# keypad-ECAD.net
KiCad netlist of a schematic drawn in EAGLE
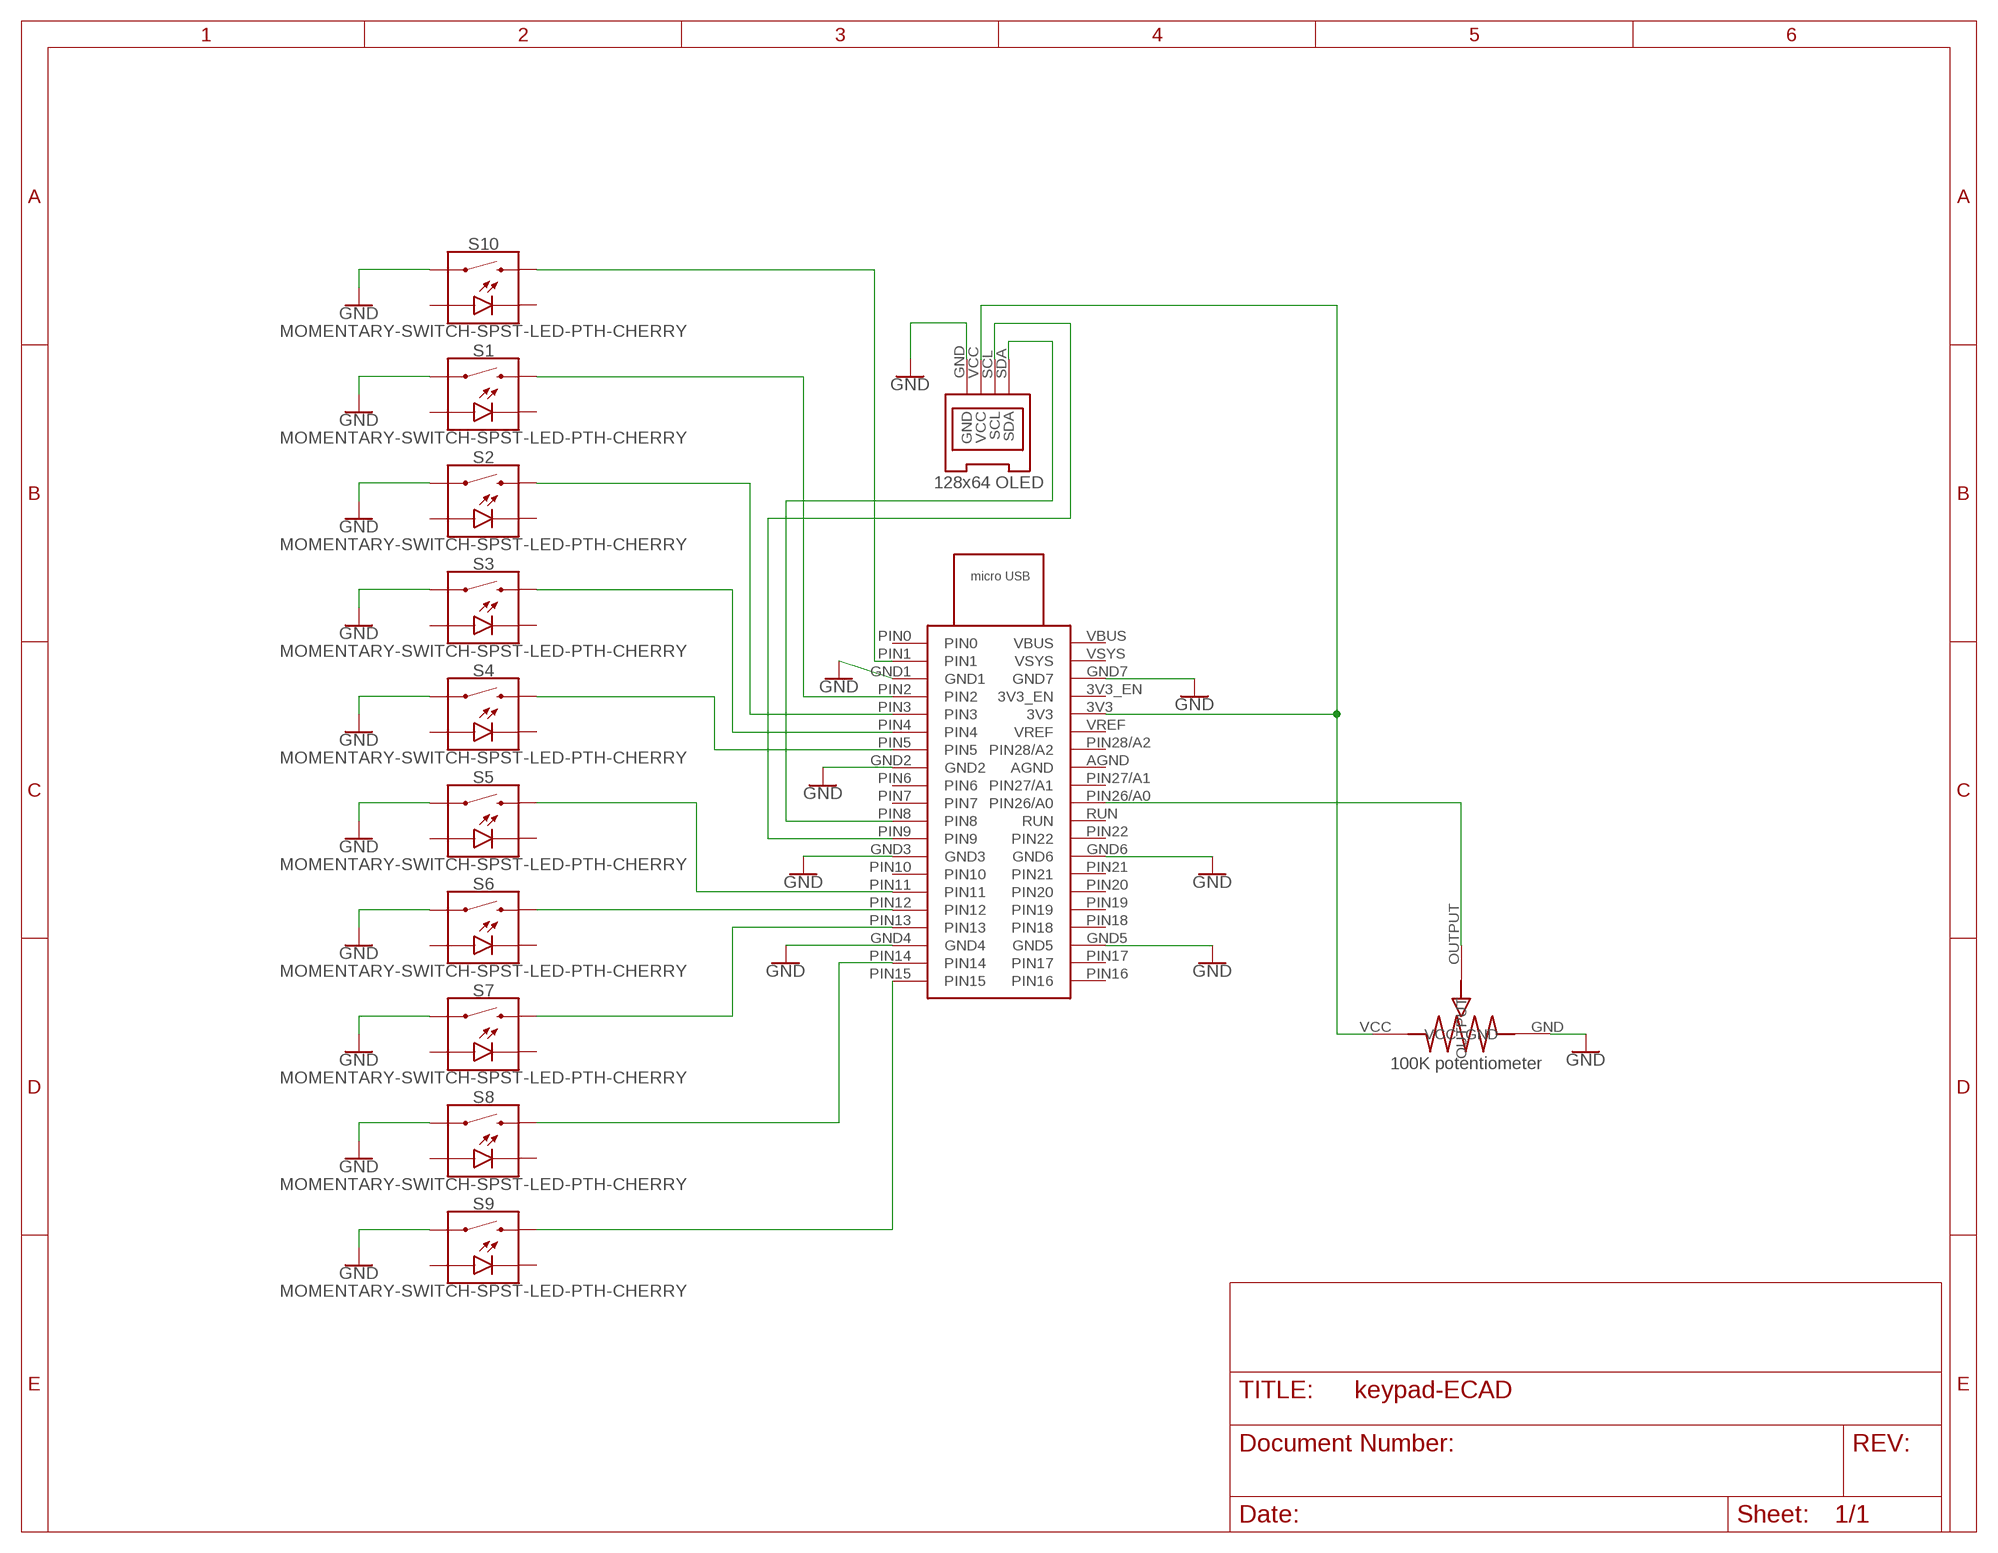
[diagram p0: schematic, sheet 1]

(export (version "E")
  (design (tool "Eeschema 10.0.6"))
  (components
    (comp (ref "S1")
      (value "MOMENTARY-SWITCH-SPST-LED-PTH-CHERRY")
      (footprint "eagle-import:CHERRY-MX-LED")
      (libsource (lib "eagle-import") (part "MOMENTARY-SWITCH-SPST-LED-PTH-CHERRY"))
    )
    (comp (ref "S2")
      (value "MOMENTARY-SWITCH-SPST-LED-PTH-CHERRY")
      (footprint "eagle-import:CHERRY-MX-LED")
      (libsource (lib "eagle-import") (part "MOMENTARY-SWITCH-SPST-LED-PTH-CHERRY"))
    )
    (comp (ref "S3")
      (value "MOMENTARY-SWITCH-SPST-LED-PTH-CHERRY")
      (footprint "eagle-import:CHERRY-MX-LED")
      (libsource (lib "eagle-import") (part "MOMENTARY-SWITCH-SPST-LED-PTH-CHERRY"))
    )
    (comp (ref "S4")
      (value "MOMENTARY-SWITCH-SPST-LED-PTH-CHERRY")
      (footprint "eagle-import:CHERRY-MX-LED")
      (libsource (lib "eagle-import") (part "MOMENTARY-SWITCH-SPST-LED-PTH-CHERRY"))
    )
    (comp (ref "S5")
      (value "MOMENTARY-SWITCH-SPST-LED-PTH-CHERRY")
      (footprint "eagle-import:CHERRY-MX-LED")
      (libsource (lib "eagle-import") (part "MOMENTARY-SWITCH-SPST-LED-PTH-CHERRY"))
    )
    (comp (ref "S6")
      (value "MOMENTARY-SWITCH-SPST-LED-PTH-CHERRY")
      (footprint "eagle-import:CHERRY-MX-LED")
      (libsource (lib "eagle-import") (part "MOMENTARY-SWITCH-SPST-LED-PTH-CHERRY"))
    )
    (comp (ref "S7")
      (value "MOMENTARY-SWITCH-SPST-LED-PTH-CHERRY")
      (footprint "eagle-import:CHERRY-MX-LED")
      (libsource (lib "eagle-import") (part "MOMENTARY-SWITCH-SPST-LED-PTH-CHERRY"))
    )
    (comp (ref "S8")
      (value "MOMENTARY-SWITCH-SPST-LED-PTH-CHERRY")
      (footprint "eagle-import:CHERRY-MX-LED")
      (libsource (lib "eagle-import") (part "MOMENTARY-SWITCH-SPST-LED-PTH-CHERRY"))
    )
    (comp (ref "S9")
      (value "MOMENTARY-SWITCH-SPST-LED-PTH-CHERRY")
      (footprint "eagle-import:CHERRY-MX-LED")
      (libsource (lib "eagle-import") (part "MOMENTARY-SWITCH-SPST-LED-PTH-CHERRY"))
    )
    (comp (ref "S10")
      (value "MOMENTARY-SWITCH-SPST-LED-PTH-CHERRY")
      (footprint "eagle-import:CHERRY-MX-LED")
      (libsource (lib "eagle-import") (part "MOMENTARY-SWITCH-SPST-LED-PTH-CHERRY"))
    )
    (comp (ref "U$1")
      (value "RP-PICO")
      (footprint "eagle-import:RP-PICO")
      (libsource (lib "eagle-import") (part "RP-PICO"))
    )
    (comp (ref "U$2")
      (value "128X64-I2C-OLED")
      (footprint "eagle-import:128X64-I2C-OLED")
      (libsource (lib "eagle-import") (part "128X64-I2C-OLED"))
    )
    (comp (ref "U$3")
      (value "KEYPAD_POT")
      (footprint "eagle-import:KEYPAD_POT")
      (libsource (lib "eagle-import") (part "KEYPAD_POT"))
    )
  )
  (nets
    (net (code "1") (name "GND") (class "Default")
      (node (ref "S1") (pin "S1") (pinfunction "1_S1") (pintype "passive"))
      (node (ref "S10") (pin "S1") (pinfunction "1_S1") (pintype "passive"))
      (node (ref "S2") (pin "S1") (pinfunction "1_S1") (pintype "passive"))
      (node (ref "S3") (pin "S1") (pinfunction "1_S1") (pintype "passive"))
      (node (ref "S4") (pin "S1") (pinfunction "1_S1") (pintype "passive"))
      (node (ref "S5") (pin "S1") (pinfunction "1_S1") (pintype "passive"))
      (node (ref "S6") (pin "S1") (pinfunction "1_S1") (pintype "passive"))
      (node (ref "S7") (pin "S1") (pinfunction "1_S1") (pintype "passive"))
      (node (ref "S8") (pin "S1") (pinfunction "1_S1") (pintype "passive"))
      (node (ref "S9") (pin "S1") (pinfunction "1_S1") (pintype "passive"))
      (node (ref "U$1") (pin "GND1") (pinfunction "GND1_GND1") (pintype "bidirectional"))
      (node (ref "U$1") (pin "GND2") (pinfunction "GND2_GND2") (pintype "bidirectional"))
      (node (ref "U$1") (pin "GND3") (pinfunction "GND3_GND3") (pintype "bidirectional"))
      (node (ref "U$1") (pin "GND4") (pinfunction "GND4_GND4") (pintype "bidirectional"))
      (node (ref "U$1") (pin "GND5") (pinfunction "GND5_GND5") (pintype "bidirectional"))
      (node (ref "U$1") (pin "GND6") (pinfunction "GND6_GND6") (pintype "bidirectional"))
      (node (ref "U$1") (pin "GND7") (pinfunction "GND7_GND7") (pintype "bidirectional"))
      (node (ref "U$2") (pin "GND") (pinfunction "GND_GND") (pintype "bidirectional"))
      (node (ref "U$3") (pin "GND") (pinfunction "GND_GND") (pintype "bidirectional"))
    )
    (net (code "2") (name "Net-(S1-2)") (class "Default")
      (node (ref "S1") (pin "S2") (pinfunction "2_S2") (pintype "passive"))
      (node (ref "U$1") (pin "PIN2") (pinfunction "PIN2_PIN2") (pintype "bidirectional"))
    )
    (net (code "3") (name "Net-(S2-2)") (class "Default")
      (node (ref "S2") (pin "S2") (pinfunction "2_S2") (pintype "passive"))
      (node (ref "U$1") (pin "PIN3") (pinfunction "PIN3_PIN3") (pintype "bidirectional"))
    )
    (net (code "4") (name "Net-(S3-2)") (class "Default")
      (node (ref "S3") (pin "S2") (pinfunction "2_S2") (pintype "passive"))
      (node (ref "U$1") (pin "PIN4") (pinfunction "PIN4_PIN4") (pintype "bidirectional"))
    )
    (net (code "5") (name "Net-(S4-2)") (class "Default")
      (node (ref "S4") (pin "S2") (pinfunction "2_S2") (pintype "passive"))
      (node (ref "U$1") (pin "PIN5") (pinfunction "PIN5_PIN5") (pintype "bidirectional"))
    )
    (net (code "6") (name "Net-(S5-2)") (class "Default")
      (node (ref "S5") (pin "S2") (pinfunction "2_S2") (pintype "passive"))
      (node (ref "U$1") (pin "PIN11") (pinfunction "PIN11_PIN11") (pintype "bidirectional"))
    )
    (net (code "7") (name "Net-(S6-2)") (class "Default")
      (node (ref "S6") (pin "S2") (pinfunction "2_S2") (pintype "passive"))
      (node (ref "U$1") (pin "PIN12") (pinfunction "PIN12_PIN12") (pintype "bidirectional"))
    )
    (net (code "8") (name "Net-(S7-2)") (class "Default")
      (node (ref "S7") (pin "S2") (pinfunction "2_S2") (pintype "passive"))
      (node (ref "U$1") (pin "PIN13") (pinfunction "PIN13_PIN13") (pintype "bidirectional"))
    )
    (net (code "9") (name "Net-(S8-2)") (class "Default")
      (node (ref "S8") (pin "S2") (pinfunction "2_S2") (pintype "passive"))
      (node (ref "U$1") (pin "PIN14") (pinfunction "PIN14_PIN14") (pintype "bidirectional"))
    )
    (net (code "10") (name "Net-(S9-2)") (class "Default")
      (node (ref "S9") (pin "S2") (pinfunction "2_S2") (pintype "passive"))
      (node (ref "U$1") (pin "PIN15") (pinfunction "PIN15_PIN15") (pintype "bidirectional"))
    )
    (net (code "11") (name "Net-(S10-2)") (class "Default")
      (node (ref "S10") (pin "S2") (pinfunction "2_S2") (pintype "passive"))
      (node (ref "U$1") (pin "PIN1") (pinfunction "PIN1_PIN1") (pintype "bidirectional"))
    )
    (net (code "12") (name "Net-(U$1-Pad3V3)") (class "Default")
      (node (ref "U$1") (pin "3V3") (pinfunction "3V3_3V3") (pintype "bidirectional"))
      (node (ref "U$2") (pin "VCC") (pinfunction "VCC_VCC") (pintype "bidirectional"))
      (node (ref "U$3") (pin "VCC") (pinfunction "VCC_VCC") (pintype "bidirectional"))
    )
    (net (code "13") (name "Net-(U$1-PadPIN8)") (class "Default")
      (node (ref "U$1") (pin "PIN8") (pinfunction "PIN8_PIN8") (pintype "bidirectional"))
      (node (ref "U$2") (pin "SDA") (pinfunction "SDA_SDA") (pintype "bidirectional"))
    )
    (net (code "14") (name "Net-(U$1-PadPIN9)") (class "Default")
      (node (ref "U$1") (pin "PIN9") (pinfunction "PIN9_PIN9") (pintype "bidirectional"))
      (node (ref "U$2") (pin "SCL") (pinfunction "SCL_SCL") (pintype "bidirectional"))
    )
    (net (code "15") (name "Net-(U$1-PadPIN26{slash}A0)") (class "Default")
      (node (ref "U$1") (pin "PIN26/A0") (pinfunction "PIN26/A0_PIN26/A0") (pintype "bidirectional"))
      (node (ref "U$3") (pin "OUTPUT") (pinfunction "OUTPUT_OUTPUT") (pintype "bidirectional"))
    )
    (net (code "16") (name "unconnected-(S1-C-PadK)") (class "Default")
      (node (ref "S1") (pin "K") (pinfunction "C_K") (pintype "passive"))
    )
    (net (code "17") (name "unconnected-(S1-PadA)") (class "Default")
      (node (ref "S1") (pin "A") (pinfunction "A_A") (pintype "passive"))
    )
    (net (code "18") (name "unconnected-(S2-C-PadK)") (class "Default")
      (node (ref "S2") (pin "K") (pinfunction "C_K") (pintype "passive"))
    )
    (net (code "19") (name "unconnected-(S2-PadA)") (class "Default")
      (node (ref "S2") (pin "A") (pinfunction "A_A") (pintype "passive"))
    )
    (net (code "20") (name "unconnected-(S3-C-PadK)") (class "Default")
      (node (ref "S3") (pin "K") (pinfunction "C_K") (pintype "passive"))
    )
    (net (code "21") (name "unconnected-(S3-PadA)") (class "Default")
      (node (ref "S3") (pin "A") (pinfunction "A_A") (pintype "passive"))
    )
    (net (code "22") (name "unconnected-(S4-C-PadK)") (class "Default")
      (node (ref "S4") (pin "K") (pinfunction "C_K") (pintype "passive"))
    )
    (net (code "23") (name "unconnected-(S4-PadA)") (class "Default")
      (node (ref "S4") (pin "A") (pinfunction "A_A") (pintype "passive"))
    )
    (net (code "24") (name "unconnected-(S5-C-PadK)") (class "Default")
      (node (ref "S5") (pin "K") (pinfunction "C_K") (pintype "passive"))
    )
    (net (code "25") (name "unconnected-(S5-PadA)") (class "Default")
      (node (ref "S5") (pin "A") (pinfunction "A_A") (pintype "passive"))
    )
    (net (code "26") (name "unconnected-(S6-C-PadK)") (class "Default")
      (node (ref "S6") (pin "K") (pinfunction "C_K") (pintype "passive"))
    )
    (net (code "27") (name "unconnected-(S6-PadA)") (class "Default")
      (node (ref "S6") (pin "A") (pinfunction "A_A") (pintype "passive"))
    )
    (net (code "28") (name "unconnected-(S7-C-PadK)") (class "Default")
      (node (ref "S7") (pin "K") (pinfunction "C_K") (pintype "passive"))
    )
    (net (code "29") (name "unconnected-(S7-PadA)") (class "Default")
      (node (ref "S7") (pin "A") (pinfunction "A_A") (pintype "passive"))
    )
    (net (code "30") (name "unconnected-(S8-C-PadK)") (class "Default")
      (node (ref "S8") (pin "K") (pinfunction "C_K") (pintype "passive"))
    )
    (net (code "31") (name "unconnected-(S8-PadA)") (class "Default")
      (node (ref "S8") (pin "A") (pinfunction "A_A") (pintype "passive"))
    )
    (net (code "32") (name "unconnected-(S9-C-PadK)") (class "Default")
      (node (ref "S9") (pin "K") (pinfunction "C_K") (pintype "passive"))
    )
    (net (code "33") (name "unconnected-(S9-PadA)") (class "Default")
      (node (ref "S9") (pin "A") (pinfunction "A_A") (pintype "passive"))
    )
    (net (code "34") (name "unconnected-(S10-C-PadK)") (class "Default")
      (node (ref "S10") (pin "K") (pinfunction "C_K") (pintype "passive"))
    )
    (net (code "35") (name "unconnected-(S10-PadA)") (class "Default")
      (node (ref "S10") (pin "A") (pinfunction "A_A") (pintype "passive"))
    )
    (net (code "36") (name "unconnected-(U$1-Pad3V3_EN)") (class "Default")
      (node (ref "U$1") (pin "3V3_EN") (pinfunction "3V3_EN_3V3_EN") (pintype "bidirectional"))
    )
    (net (code "37") (name "unconnected-(U$1-PadAGND)") (class "Default")
      (node (ref "U$1") (pin "AGND") (pinfunction "AGND_AGND") (pintype "bidirectional"))
    )
    (net (code "38") (name "unconnected-(U$1-PadPIN0)") (class "Default")
      (node (ref "U$1") (pin "PIN0") (pinfunction "PIN0_PIN0") (pintype "bidirectional"))
    )
    (net (code "39") (name "unconnected-(U$1-PadPIN6)") (class "Default")
      (node (ref "U$1") (pin "PIN6") (pinfunction "PIN6_PIN6") (pintype "bidirectional"))
    )
    (net (code "40") (name "unconnected-(U$1-PadPIN7)") (class "Default")
      (node (ref "U$1") (pin "PIN7") (pinfunction "PIN7_PIN7") (pintype "bidirectional"))
    )
    (net (code "41") (name "unconnected-(U$1-PadPIN10)") (class "Default")
      (node (ref "U$1") (pin "PIN10") (pinfunction "PIN10_PIN10") (pintype "bidirectional"))
    )
    (net (code "42") (name "unconnected-(U$1-PadPIN16)") (class "Default")
      (node (ref "U$1") (pin "PIN16") (pinfunction "PIN16_PIN16") (pintype "bidirectional"))
    )
    (net (code "43") (name "unconnected-(U$1-PadPIN17)") (class "Default")
      (node (ref "U$1") (pin "PIN17") (pinfunction "PIN17_PIN17") (pintype "bidirectional"))
    )
    (net (code "44") (name "unconnected-(U$1-PadPIN18)") (class "Default")
      (node (ref "U$1") (pin "PIN18") (pinfunction "PIN18_PIN18") (pintype "bidirectional"))
    )
    (net (code "45") (name "unconnected-(U$1-PadPIN19)") (class "Default")
      (node (ref "U$1") (pin "PIN19") (pinfunction "PIN19_PIN19") (pintype "bidirectional"))
    )
    (net (code "46") (name "unconnected-(U$1-PadPIN20)") (class "Default")
      (node (ref "U$1") (pin "PIN20") (pinfunction "PIN20_PIN20") (pintype "bidirectional"))
    )
    (net (code "47") (name "unconnected-(U$1-PadPIN21)") (class "Default")
      (node (ref "U$1") (pin "PIN21") (pinfunction "PIN21_PIN21") (pintype "bidirectional"))
    )
    (net (code "48") (name "unconnected-(U$1-PadPIN22)") (class "Default")
      (node (ref "U$1") (pin "PIN22") (pinfunction "PIN22_PIN22") (pintype "bidirectional"))
    )
    (net (code "49") (name "unconnected-(U$1-PadPIN27{slash}A1)") (class "Default")
      (node (ref "U$1") (pin "PIN27/A1") (pinfunction "PIN27/A1_PIN27/A1") (pintype "bidirectional"))
    )
    (net (code "50") (name "unconnected-(U$1-PadPIN28{slash}A2)") (class "Default")
      (node (ref "U$1") (pin "PIN28/A2") (pinfunction "PIN28/A2_PIN28/A2") (pintype "bidirectional"))
    )
    (net (code "51") (name "unconnected-(U$1-PadRUN)") (class "Default")
      (node (ref "U$1") (pin "RUN") (pinfunction "RUN_RUN") (pintype "bidirectional"))
    )
    (net (code "52") (name "unconnected-(U$1-PadVBUS)") (class "Default")
      (node (ref "U$1") (pin "VBUS") (pinfunction "VBUS_VBUS") (pintype "bidirectional"))
    )
    (net (code "53") (name "unconnected-(U$1-PadVREF)") (class "Default")
      (node (ref "U$1") (pin "VREF") (pinfunction "VREF_VREF") (pintype "bidirectional"))
    )
    (net (code "54") (name "unconnected-(U$1-PadVSYS)") (class "Default")
      (node (ref "U$1") (pin "VSYS") (pinfunction "VSYS_VSYS") (pintype "bidirectional"))
    )
  )
)
